# TE7300.net
KiCad netlist of a schematic drawn in Altium Designer
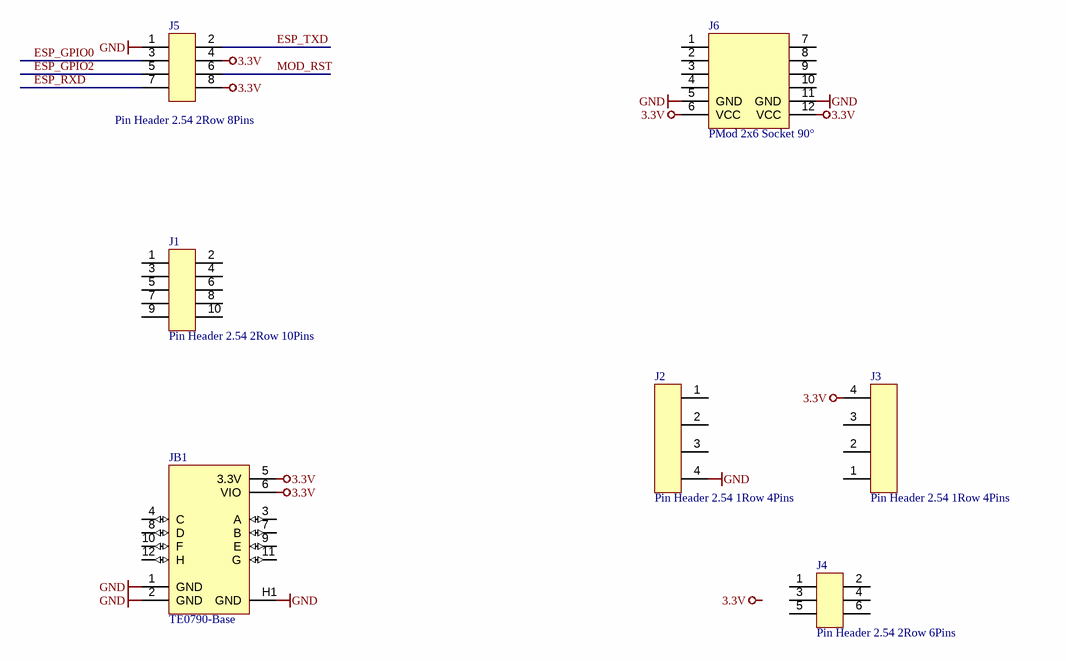
[diagram p0: TE7300.SchDoc]

(export (version "E")
  (design (tool "Eeschema 10.0.6"))
  (components
    (comp (ref "J1")
      (value "Pin Header 2.54 2Row 10Pins")
      (footprint "STIFTLEISTE2_54 OG 2R-10")
      (description "Stiftleiste gerade 2-reihig, 10pol.")
      (libsource (lib "TE") (part "CON-10"))
    )
    (comp (ref "J2")
      (value "Pin Header 2.54 1Row 4Pins")
      (footprint "STIFTLEISTE2_54 OG 1R-4")
      (description "Stiftleiste gerade 1-reihig, 4pol.")
      (libsource (lib "") (part "CON-4_1"))
    )
    (comp (ref "J3")
      (value "Pin Header 2.54 1Row 4Pins")
      (footprint "STIFTLEISTE2_54 OG 1R-4")
      (description "Stiftleiste gerade 1-reihig, 4pol.")
      (libsource (lib "TE") (part "CON-4"))
    )
    (comp (ref "J4")
      (value "Pin Header 2.54 2Row 6Pins")
      (footprint "STIFTLEISTE2_54 OG 2R-6")
      (description "Stiftleiste gerade 2-reihig, 6pol.")
      (libsource (lib "TE") (part "CON-6"))
    )
    (comp (ref "J5")
      (value "Pin Header 2.54 2Row 8Pins")
      (footprint "STIFTLEISTE2_54 OG 2R-8")
      (description "Stiftleiste gerade 2-reihig, 8pol.")
      (libsource (lib "TE") (part "CON-8"))
    )
    (comp (ref "J6")
      (value "PMod 2x6 Socket 90°")
      (footprint "PMod2x6")
      (libsource (lib "TE") (part "PMod2x6"))
    )
    (comp (ref "JB1")
      (value "TE0790-Base")
      (footprint "TE0790-Base")
      (libsource (lib "TE") (part "TE0790-JB"))
    )
  )
  (nets
    (net (code "1") (name "/ESP_GPIO0") (class "Default") (node (ref "J5") (pin "3") (pintype "passive")))
    (net (code "2") (name "/ESP_GPIO2") (class "Default") (node (ref "J5") (pin "5") (pintype "passive")))
    (net (code "3") (name "/ESP_RXD") (class "Default") (node (ref "J5") (pin "7") (pintype "passive")))
    (net (code "4") (name "/ESP_TXD") (class "Default") (node (ref "J5") (pin "2") (pintype "passive")))
    (net (code "5") (name "/MOD_RST") (class "Default") (node (ref "J5") (pin "6") (pintype "passive")))
    (net (code "6") (name "3.3V") (class "Default")
      (node (ref "J3") (pin "4") (pintype "passive"))
      (node (ref "J5") (pin "4") (pintype "passive"))
      (node (ref "J5") (pin "8") (pintype "passive"))
      (node (ref "J6") (pin "12") (pinfunction "VCC_12") (pintype "power_in"))
      (node (ref "J6") (pin "6") (pinfunction "VCC_6") (pintype "power_in"))
      (node (ref "JB1") (pin "5") (pinfunction "3.3V_5") (pintype "power_in"))
      (node (ref "JB1") (pin "6") (pinfunction "VIO_6") (pintype "power_in"))
    )
    (net (code "7") (name "GND") (class "Default")
      (node (ref "J2") (pin "4") (pintype "passive"))
      (node (ref "J5") (pin "1") (pintype "passive"))
      (node (ref "J6") (pin "11") (pinfunction "GND_11") (pintype "power_in"))
      (node (ref "J6") (pin "5") (pinfunction "GND_5") (pintype "power_in"))
      (node (ref "JB1") (pin "1") (pinfunction "GND_1") (pintype "power_in"))
      (node (ref "JB1") (pin "2") (pinfunction "GND_2") (pintype "power_in"))
      (node (ref "JB1") (pin "H1") (pinfunction "GND_H1") (pintype "power_in"))
    )
    (net (code "8") (name "unconnected-(J1-Pad1)") (class "Default")
      (node (ref "J1") (pin "1") (pinfunction "1_1") (pintype "passive"))
    )
    (net (code "9") (name "unconnected-(J1-Pad2)") (class "Default")
      (node (ref "J1") (pin "2") (pinfunction "2_2") (pintype "passive"))
    )
    (net (code "10") (name "unconnected-(J1-Pad3)") (class "Default")
      (node (ref "J1") (pin "3") (pinfunction "3_3") (pintype "passive"))
    )
    (net (code "11") (name "unconnected-(J1-Pad4)") (class "Default")
      (node (ref "J1") (pin "4") (pinfunction "4_4") (pintype "passive"))
    )
    (net (code "12") (name "unconnected-(J1-Pad5)") (class "Default")
      (node (ref "J1") (pin "5") (pinfunction "5_5") (pintype "passive"))
    )
    (net (code "13") (name "unconnected-(J1-Pad6)") (class "Default")
      (node (ref "J1") (pin "6") (pinfunction "6_6") (pintype "passive"))
    )
    (net (code "14") (name "unconnected-(J1-Pad7)") (class "Default")
      (node (ref "J1") (pin "7") (pinfunction "7_7") (pintype "passive"))
    )
    (net (code "15") (name "unconnected-(J1-Pad8)") (class "Default")
      (node (ref "J1") (pin "8") (pinfunction "8_8") (pintype "passive"))
    )
    (net (code "16") (name "unconnected-(J1-Pad9)") (class "Default")
      (node (ref "J1") (pin "9") (pinfunction "9_9") (pintype "passive"))
    )
    (net (code "17") (name "unconnected-(J1-Pad10)") (class "Default")
      (node (ref "J1") (pin "10") (pinfunction "10_10") (pintype "passive"))
    )
    (net (code "18") (name "unconnected-(J2-Pad1)") (class "Default")
      (node (ref "J2") (pin "1") (pintype "passive"))
    )
    (net (code "19") (name "unconnected-(J2-Pad2)") (class "Default")
      (node (ref "J2") (pin "2") (pintype "passive"))
    )
    (net (code "20") (name "unconnected-(J2-Pad3)") (class "Default")
      (node (ref "J2") (pin "3") (pintype "passive"))
    )
    (net (code "21") (name "unconnected-(J3-Pad1)") (class "Default")
      (node (ref "J3") (pin "1") (pintype "passive"))
    )
    (net (code "22") (name "unconnected-(J3-Pad2)") (class "Default")
      (node (ref "J3") (pin "2") (pintype "passive"))
    )
    (net (code "23") (name "unconnected-(J3-Pad3)") (class "Default")
      (node (ref "J3") (pin "3") (pintype "passive"))
    )
    (net (code "24") (name "unconnected-(J4-Pad1)") (class "Default")
      (node (ref "J4") (pin "1") (pintype "passive"))
    )
    (net (code "25") (name "unconnected-(J4-Pad2)") (class "Default")
      (node (ref "J4") (pin "2") (pintype "passive"))
    )
    (net (code "26") (name "unconnected-(J4-Pad3)") (class "Default")
      (node (ref "J4") (pin "3") (pintype "passive"))
    )
    (net (code "27") (name "unconnected-(J4-Pad4)") (class "Default")
      (node (ref "J4") (pin "4") (pintype "passive"))
    )
    (net (code "28") (name "unconnected-(J4-Pad5)") (class "Default")
      (node (ref "J4") (pin "5") (pintype "passive"))
    )
    (net (code "29") (name "unconnected-(J4-Pad6)") (class "Default")
      (node (ref "J4") (pin "6") (pintype "passive"))
    )
    (net (code "30") (name "unconnected-(J6-Pad1)") (class "Default")
      (node (ref "J6") (pin "1") (pintype "passive"))
    )
    (net (code "31") (name "unconnected-(J6-Pad2)") (class "Default")
      (node (ref "J6") (pin "2") (pintype "passive"))
    )
    (net (code "32") (name "unconnected-(J6-Pad3)") (class "Default")
      (node (ref "J6") (pin "3") (pintype "passive"))
    )
    (net (code "33") (name "unconnected-(J6-Pad4)") (class "Default")
      (node (ref "J6") (pin "4") (pintype "passive"))
    )
    (net (code "34") (name "unconnected-(J6-Pad7)") (class "Default")
      (node (ref "J6") (pin "7") (pintype "passive"))
    )
    (net (code "35") (name "unconnected-(J6-Pad8)") (class "Default")
      (node (ref "J6") (pin "8") (pintype "passive"))
    )
    (net (code "36") (name "unconnected-(J6-Pad9)") (class "Default")
      (node (ref "J6") (pin "9") (pintype "passive"))
    )
    (net (code "37") (name "unconnected-(J6-Pad10)") (class "Default")
      (node (ref "J6") (pin "10") (pintype "passive"))
    )
    (net (code "38") (name "unconnected-(JB1-A-Pad3)") (class "Default")
      (node (ref "JB1") (pin "3") (pinfunction "A_3") (pintype "bidirectional"))
    )
    (net (code "39") (name "unconnected-(JB1-B-Pad7)") (class "Default")
      (node (ref "JB1") (pin "7") (pinfunction "B_7") (pintype "bidirectional"))
    )
    (net (code "40") (name "unconnected-(JB1-C-Pad4)") (class "Default")
      (node (ref "JB1") (pin "4") (pinfunction "C_4") (pintype "bidirectional"))
    )
    (net (code "41") (name "unconnected-(JB1-D-Pad8)") (class "Default")
      (node (ref "JB1") (pin "8") (pinfunction "D_8") (pintype "bidirectional"))
    )
    (net (code "42") (name "unconnected-(JB1-E-Pad9)") (class "Default")
      (node (ref "JB1") (pin "9") (pinfunction "E_9") (pintype "bidirectional"))
    )
    (net (code "43") (name "unconnected-(JB1-F-Pad10)") (class "Default")
      (node (ref "JB1") (pin "10") (pinfunction "F_10") (pintype "bidirectional"))
    )
    (net (code "44") (name "unconnected-(JB1-G-Pad11)") (class "Default")
      (node (ref "JB1") (pin "11") (pinfunction "G_11") (pintype "bidirectional"))
    )
    (net (code "45") (name "unconnected-(JB1-H-Pad12)") (class "Default")
      (node (ref "JB1") (pin "12") (pinfunction "H_12") (pintype "bidirectional"))
    )
  )
)
